# USBSocket_Type8_v1_0.net
KiCad netlist of a schematic drawn in EAGLE
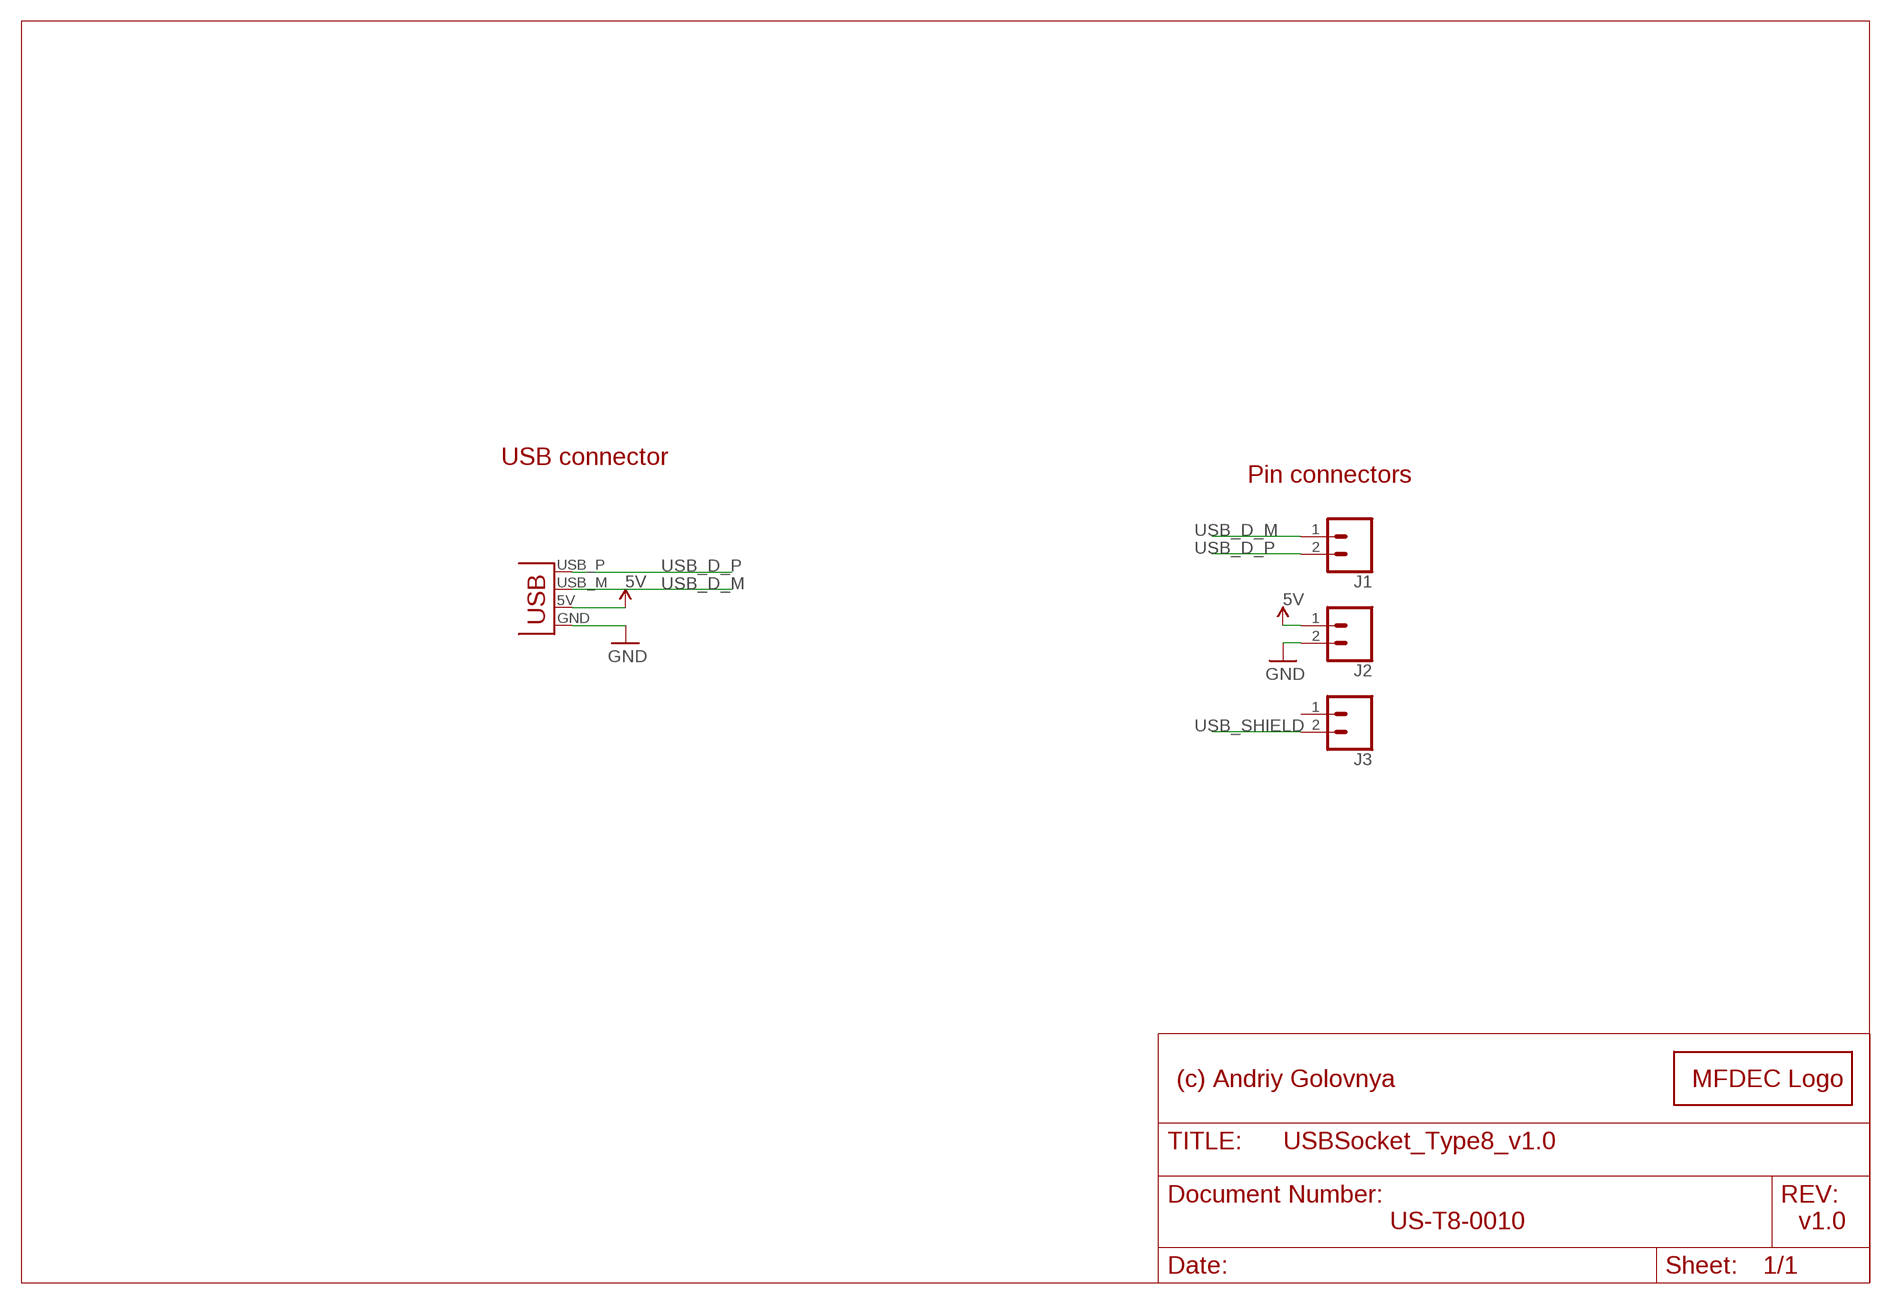
[diagram p0: schematic, sheet 1]

(export (version "E")
  (design (tool "Eeschema 10.0.6"))
  (components
    (comp (ref "J1")
      (value "CONN_02")
      (footprint "eagle-import:1X02")
      (libsource (lib "eagle-import") (part "CONN_02"))
    )
    (comp (ref "J2")
      (value "CONN_02")
      (footprint "eagle-import:1X02")
      (libsource (lib "eagle-import") (part "CONN_02"))
    )
    (comp (ref "J3")
      (value "CONN_02")
      (footprint "eagle-import:1X02")
      (libsource (lib "eagle-import") (part "CONN_02"))
    )
    (comp (ref "LOGO1")
      (value "MFDECLOGO_L_10MM")
      (footprint "eagle-import:MFDEC_L_10MM")
      (libsource (lib "eagle-import") (part "MFDECLOGO_L_10MM"))
    )
    (comp (ref "X1")
      (value "USBPCB")
      (footprint "eagle-import:USB-A-PCB")
      (libsource (lib "eagle-import") (part "USBPCB"))
    )
  )
  (nets
    (net (code "1") (name "/USB_D_M") (class "Default")
      (node (ref "J1") (pin "1") (pinfunction "1_1") (pintype "passive"))
      (node (ref "X1") (pin "USB_M") (pinfunction "D-_USB_M") (pintype "bidirectional"))
    )
    (net (code "2") (name "/USB_D_P") (class "Default")
      (node (ref "J1") (pin "2") (pinfunction "2_2") (pintype "passive"))
      (node (ref "X1") (pin "USB_P") (pinfunction "D+_USB_P") (pintype "bidirectional"))
    )
    (net (code "3") (name "/USB_SHIELD") (class "Default")
      (node (ref "J3") (pin "2") (pinfunction "2_2") (pintype "passive"))
    )
    (net (code "4") (name "5V") (class "Default")
      (node (ref "J2") (pin "1") (pinfunction "1_1") (pintype "passive"))
      (node (ref "X1") (pin "5V") (pinfunction "VBUS_5V") (pintype "bidirectional"))
    )
    (net (code "5") (name "GND") (class "Default")
      (node (ref "J2") (pin "2") (pinfunction "2_2") (pintype "passive"))
      (node (ref "X1") (pin "GND") (pinfunction "GND_GND") (pintype "bidirectional"))
    )
    (net (code "6") (name "unconnected-(J3-Pad1)") (class "Default")
      (node (ref "J3") (pin "1") (pinfunction "1_1") (pintype "passive"))
    )
  )
)
